# 12_CONSOLE.net
KiCad netlist of a schematic drawn in Altium Designer
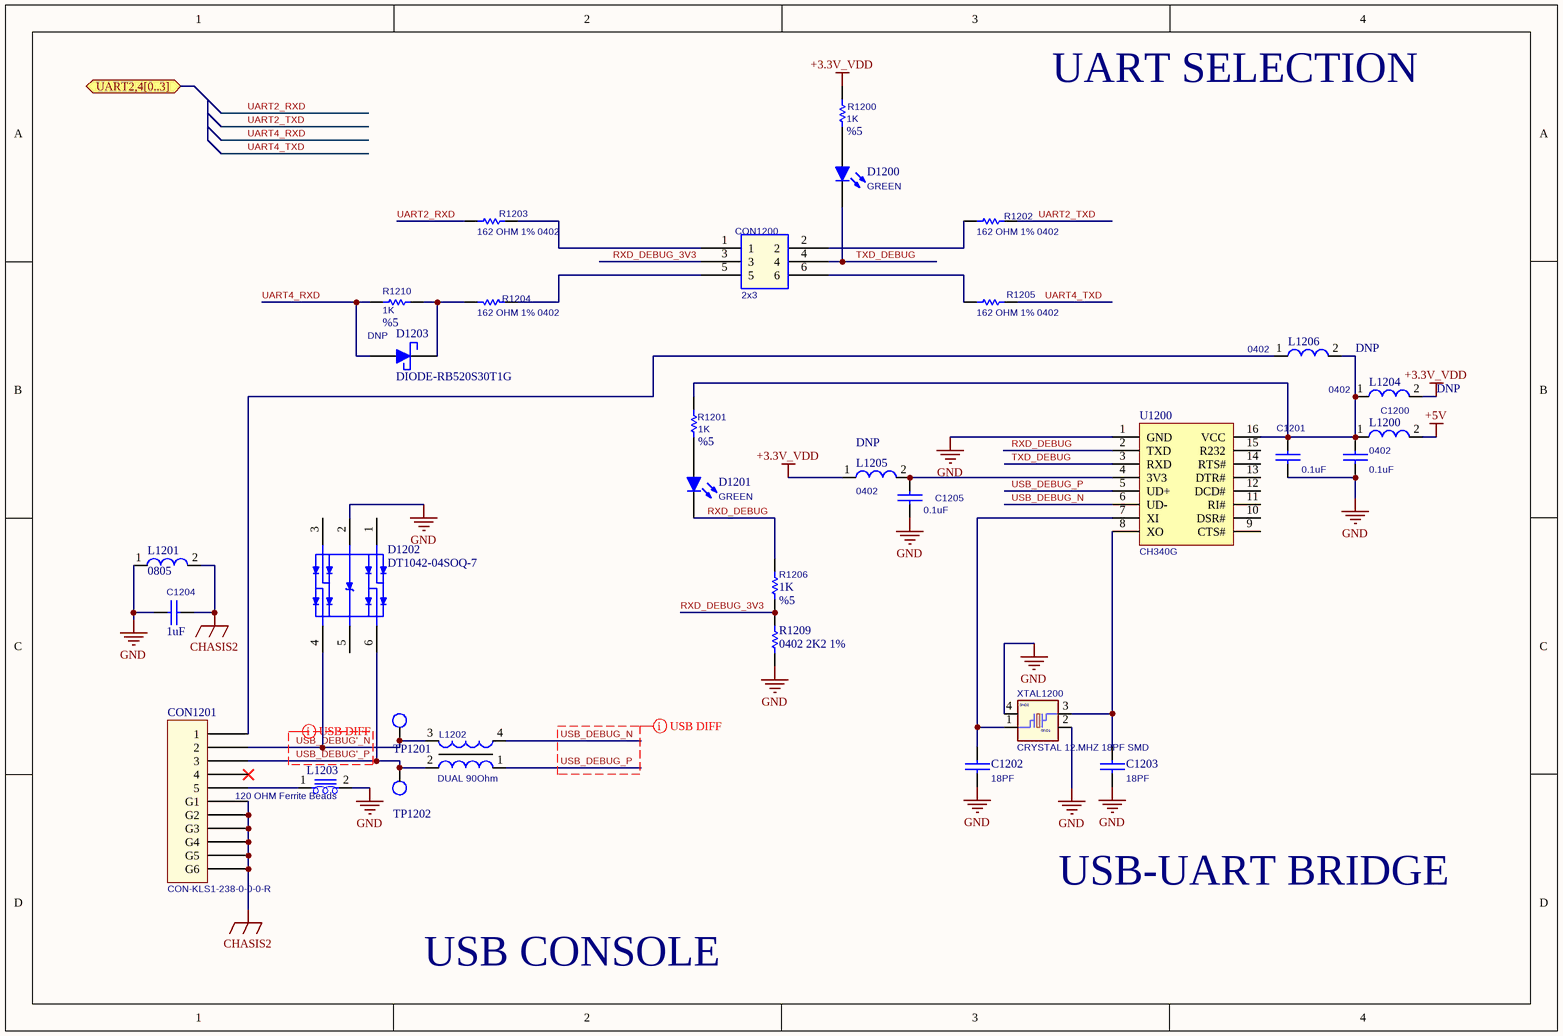
[diagram p0: 12 CONSOLE.SchDoc]

(export (version "E")
  (design (tool "Eeschema 10.0.6"))
  (components
    (comp (ref "C1200")
      (value "0.1uF")
      (footprint "0402_CC")
      (description "CAP VER 0.1UF 16V X7R 0402")
      (fields (field (name "CREATED BY") "LA") (field (name "CHECKED BY") "*"))
      (libsource (lib "ARETE_L") (part "CAP-CL05B104KO5NNNC"))
    )
    (comp (ref "C1201")
      (value "0.1uF")
      (footprint "0402_CC")
      (description "CAP VER 0.1UF 16V X7R 0402")
      (fields (field (name "CREATED BY") "LA") (field (name "CHECKED BY") "*"))
      (libsource (lib "ARETE_L") (part "CAP-CL05B104KO5NNNC"))
    )
    (comp (ref "C1202")
      (value "18PF")
      (footprint "0402_CC")
      (description "CAP CER 18PF 50V C0G/NP0 0402")
      (fields (field (name "CREATED BY") "*") (field (name "CHECKED BY") "*"))
      (libsource (lib "ARETE_SCH") (part "CAP-GCM1555C1H180JA16D"))
    )
    (comp (ref "C1203")
      (value "18PF")
      (footprint "0402_CC")
      (description "CAP CER 18PF 50V C0G/NP0 0402")
      (fields (field (name "CREATED BY") "*") (field (name "CHECKED BY") "*"))
      (libsource (lib "ARETE_SCH") (part "CAP-GCM1555C1H180JA16D"))
    )
    (comp (ref "C1204")
      (value "1uF")
      (footprint "0603_CC")
      (description "CAP CER 1UF 25V X7R 0603")
      (fields (field (name "CREATED BY") "LA") (field (name "CHECKED BY") "*"))
      (libsource (lib "ARETE_SCH") (part "CAP-CL10B105KA8NNNC"))
    )
    (comp (ref "C1205")
      (value "0.1uF")
      (footprint "0402_CC")
      (description "CAP VER 0.1UF 16V X7R 0402")
      (fields (field (name "CREATED BY") "LA") (field (name "CHECKED BY") "*"))
      (libsource (lib "ARETE_L") (part "CAP-CL05B104KO5NNNC"))
    )
    (comp (ref "CON1200")
      (value "2x3")
      (footprint "HEADER 2.54 X 3x2")
      (description "2x3 6 PIN 2.54MM HEADER")
      (fields
        (field (name "MANUFACTURER") "Wurth Electronics")
        (field (name "MANUFACTURER PART NUMBER") "61300621121")
        (field (name "CREATED BY") "*")
        (field (name "CHECKED BY") "*")
      )
      (libsource (lib "ARETE_SCH") (part "CON-6 PIN 2.54MM"))
    )
    (comp (ref "CON1201")
      (value "CON-KLS1-238-0-0-0-R")
      (footprint "KLS1-238-0-0-0-R")
      (fields (field (name "CREATED BY") "OKS,EE") (field (name "CHECKED BY") "*"))
      (libsource (lib "ARETE_SCH") (part "CON-KLS1-238-0-0-0-R"))
    )
    (comp (ref "D1200")
      (value "GREEN")
      (footprint "0603_LED")
      (description "LED SMD 0603 SUPER GREEN")
      (fields (field (name "CREATED BY") "*") (field (name "CHECKED BY") "*"))
      (libsource (lib "ARETE_SCH") (part "LED-LTST-C190KRKT"))
    )
    (comp (ref "D1201")
      (value "GREEN")
      (footprint "0603_LED")
      (description "LED SMD 0603 SUPER GREEN")
      (fields (field (name "CREATED BY") "*") (field (name "CHECKED BY") "*"))
      (libsource (lib "ARETE_SCH") (part "LED-LTST-C190KRKT"))
    )
    (comp (ref "D1202")
      (value "DT1042-04SOQ-7")
      (footprint "DIODE-DT1042-04SOQ-7")
      (description "HDMI TVS DIODE")
      (fields (field (name "CREATED BY") "E.E") (field (name "CHECKED BY") "*"))
      (libsource (lib "ARETE_SCH") (part "DIODE-DT1042-04SOQ-7"))
    )
    (comp (ref "D1203")
      (value "DIODE-RB520S30T1G")
      (footprint "SOD523")
      (description "DIODE SCHOTTKY 30V 200MA SOD523")
      (fields (field (name "CREATED BY") "LA") (field (name "CHECKED BY") "*"))
      (libsource (lib "ARETE_L") (part "DIODE-RB520S30T1G"))
    )
    (comp (ref "L1200")
      (value "0402")
      (footprint "0402_RES")
      (description "0OHM 0402")
      (fields (field (name "CREATED BY") "EE") (field (name "CHECKED BY") "*"))
      (libsource (lib "ARETE_SCH") (part "IND-FERRITE (RES 0 OHM) 0402"))
    )
    (comp (ref "L1201")
      (value "0805")
      (footprint "0805")
      (description "0OHM 0805")
      (fields (field (name "CREATED BY") "EE") (field (name "CHECKED BY") "*"))
      (libsource (lib "ARETE_SCH") (part "IND-FERRITE (RES 0 OHM) 0805"))
    )
    (comp (ref "L1202")
      (value "DUAL 90Ohm")
      (footprint "DLW21H")
      (description "Common Mode Chokes Dual 90Ohm 100MHz 0.33A 0.35Ohm DCR SMD T/R")
      (fields (field (name "CREATED BY") "E.E") (field (name "CHECKED BY") "*"))
      (libsource (lib "ARETE_SCH") (part "IND-DLW21HN900SQ2L"))
    )
    (comp (ref "L1203")
      (value "120 OHM Ferrite Beads")
      (footprint "0603_RES")
      (description "Ferrite Beads Multi-Layer 120Ohm 25% 100MHz 2A 0.05Ohm DCR 0603 Automotive T/R")
      (fields (field (name "CREATED BY") "E.E") (field (name "CHECKED BY") "*"))
      (libsource (lib "ARETE_SCH") (part "IND-BLM18PG121SH1D"))
    )
    (comp (ref "L1204")
      (value "0402")
      (footprint "0402_RES")
      (description "0OHM 0402")
      (fields
        (field (name "ASSY_OPT") "DNP")
        (field (name "CREATED BY") "EE")
        (field (name "CHECKED BY") "*")
      )
      (libsource (lib "ARETE_SCH") (part "IND-FERRITE (RES 0 OHM) 0402"))
    )
    (comp (ref "L1205")
      (value "0402")
      (footprint "0402_RES")
      (description "0OHM 0402")
      (fields
        (field (name "ASSY_OPT") "DNP")
        (field (name "CREATED BY") "EE")
        (field (name "CHECKED BY") "*")
      )
      (libsource (lib "ARETE_SCH") (part "IND-FERRITE (RES 0 OHM) 0402"))
    )
    (comp (ref "L1206")
      (value "0402")
      (footprint "0402_RES")
      (description "0OHM 0402")
      (fields
        (field (name "ASSY_OPT") "DNP")
        (field (name "CREATED BY") "EE")
        (field (name "CHECKED BY") "*")
      )
      (libsource (lib "ARETE_SCH") (part "IND-FERRITE (RES 0 OHM) 0402"))
    )
    (comp (ref "R1200")
      (value "1K")
      (footprint "0402_RES")
      (description "RES 1K OHM 5% 1/16W 0402")
      (fields
        (field (name "TOLERANCE") "%5")
        (field (name "CREATED BY") "LA")
        (field (name "CHECKED BY") "*")
      )
      (libsource (lib "ARETE_SCH") (part "RES-RMCF0402JT1K00"))
    )
    (comp (ref "R1201")
      (value "1K")
      (footprint "0402_RES")
      (description "RES 1K OHM 5% 1/16W 0402")
      (fields
        (field (name "TOLERANCE") "%5")
        (field (name "CREATED BY") "LA")
        (field (name "CHECKED BY") "*")
      )
      (libsource (lib "ARETE_SCH") (part "RES-RMCF0402JT1K00"))
    )
    (comp (ref "R1202")
      (value "162 OHM 1% 0402")
      (footprint "0402_RES")
      (description "162 ±1% 0.1W, 1/10W Chip Resistor 0402 (1005 Metric) Automotive AEC-Q200 Thick Film")
      (fields (field (name "CREATED BY") "E.E") (field (name "CHECKED BY") "*"))
      (libsource (lib "ARETE_SCH") (part "RES-ERJ-2RKF1620X"))
    )
    (comp (ref "R1203")
      (value "162 OHM 1% 0402")
      (footprint "0402_RES")
      (description "162 ±1% 0.1W, 1/10W Chip Resistor 0402 (1005 Metric) Automotive AEC-Q200 Thick Film")
      (fields (field (name "CREATED BY") "E.E") (field (name "CHECKED BY") "*"))
      (libsource (lib "ARETE_SCH") (part "RES-ERJ-2RKF1620X"))
    )
    (comp (ref "R1204")
      (value "162 OHM 1% 0402")
      (footprint "0402_RES")
      (description "162 ±1% 0.1W, 1/10W Chip Resistor 0402 (1005 Metric) Automotive AEC-Q200 Thick Film")
      (fields (field (name "CREATED BY") "E.E") (field (name "CHECKED BY") "*"))
      (libsource (lib "ARETE_SCH") (part "RES-ERJ-2RKF1620X"))
    )
    (comp (ref "R1205")
      (value "162 OHM 1% 0402")
      (footprint "0402_RES")
      (description "162 ±1% 0.1W, 1/10W Chip Resistor 0402 (1005 Metric) Automotive AEC-Q200 Thick Film")
      (fields (field (name "CREATED BY") "E.E") (field (name "CHECKED BY") "*"))
      (libsource (lib "ARETE_SCH") (part "RES-ERJ-2RKF1620X"))
    )
    (comp (ref "R1206")
      (value "1K")
      (footprint "0402_RES")
      (description "RES 1K OHM 5% 1/16W 0402")
      (fields
        (field (name "TOLERANCE") "%5")
        (field (name "CREATED BY") "LA")
        (field (name "CHECKED BY") "*")
      )
      (libsource (lib "ARETE_SCH") (part "RES-RMCF0402JT1K00"))
    )
    (comp (ref "R1209")
      (value "0402 2K2 1%")
      (footprint "0402_RES")
      (fields (field (name "CREATED BY") "E.E") (field (name "CHECKED BY") "*"))
      (libsource (lib "ARETE_V2_SCH") (part "RES-CRGCQ0402F2K2"))
    )
    (comp (ref "R1210")
      (value "1K")
      (footprint "0402_RES")
      (description "RES 1K OHM 5% 1/16W 0402")
      (fields
        (field (name "ASSY_OPT") "DNP")
        (field (name "TOLERANCE") "%5")
        (field (name "CREATED BY") "LA")
        (field (name "CHECKED BY") "*")
      )
      (libsource (lib "ARETE_SCH") (part "RES-RMCF0402JT1K00"))
    )
    (comp (ref "TP1201")
      (value "TEST POINT 15")
      (footprint "testpoint_15")
      (libsource (lib "ARETE_L") (part "TEST POINT 15"))
    )
    (comp (ref "TP1202")
      (value "TEST POINT 15")
      (footprint "testpoint_15")
      (libsource (lib "ARETE_L") (part "TEST POINT 15"))
    )
    (comp (ref "U1200")
      (value "CH340G")
      (footprint "CH340G")
      (description "IC-340 USB INTERFACE SO16")
      (fields (field (name "CREATED BY") "E.E.") (field (name "CHECKED BY") "*"))
      (libsource (lib "ARETE_SCH") (part "IC-CH340G"))
    )
    (comp (ref "XTAL1200")
      (value "CRYSTAL 12.MHZ 18PF SMD")
      (footprint "XTLOSC4_3P2X2P5MM_SM")
      (description "CRYSTAL 12.0000MHZ 18PF SMD")
      (fields (field (name "CREATED BY") "E.E") (field (name "CHECKED BY") "*"))
      (libsource (lib "ARETE_SCH") (part "XTAL-FA-238V 12.0000MB50X-C0"))
    )
  )
  (nets
    (net (code "5") (name "+3.3V_VDD") (class "Default")
      (node (ref "L1204") (pin "2") (pinfunction "2_2") (pintype "passive"))
      (node (ref "L1205") (pin "1") (pinfunction "1_1") (pintype "passive"))
      (node (ref "R1200") (pin "1") (pinfunction "1_1") (pintype "passive"))
    )
    (net (code "6") (name "+5V") (class "Default")
      (node (ref "L1200") (pin "2") (pinfunction "2_2") (pintype "passive"))
    )
    (net (code "7") (name "/RXD_DEBUG") (class "Default")
      (node (ref "D1201") (pin "2") (pinfunction "K_2") (pintype "passive"))
      (node (ref "R1206") (pin "2") (pinfunction "2_2") (pintype "passive"))
      (node (ref "U1200") (pin "2") (pinfunction "TXD_2") (pintype "passive"))
    )
    (net (code "8") (name "/RXD_DEBUG_3V3") (class "Default")
      (node (ref "CON1200") (pin "3") (pinfunction "3_3") (pintype "passive"))
      (node (ref "R1206") (pin "1") (pinfunction "1_1") (pintype "passive"))
      (node (ref "R1209") (pin "2") (pinfunction "2_2") (pintype "passive"))
    )
    (net (code "9") (name "/TXD_DEBUG") (class "Default")
      (node (ref "CON1200") (pin "4") (pinfunction "4_4") (pintype "passive"))
      (node (ref "D1200") (pin "2") (pinfunction "K_2") (pintype "passive"))
      (node (ref "U1200") (pin "3") (pinfunction "RXD_3") (pintype "passive"))
    )
    (net (code "11") (name "/UART2_RXD") (class "Default")
      (node (ref "R1203") (pin "1") (pinfunction "1_1") (pintype "passive"))
    )
    (net (code "12") (name "/UART2_TXD") (class "Default")
      (node (ref "R1202") (pin "2") (pinfunction "2_2") (pintype "passive"))
    )
    (net (code "13") (name "/UART4_RXD") (class "Default")
      (node (ref "D1203") (pin "1") (pinfunction "A_1") (pintype "passive"))
      (node (ref "R1210") (pin "1") (pinfunction "1_1") (pintype "passive"))
    )
    (net (code "14") (name "/UART4_TXD") (class "Default")
      (node (ref "R1205") (pin "2") (pinfunction "2_2") (pintype "passive"))
    )
    (net (code "15") (name "/USB_DEBUG'_N") (class "Default")
      (node (ref "CON1201") (pin "2") (pinfunction "2_2") (pintype "passive"))
      (node (ref "D1202") (pin "4") (pinfunction "IO3_4") (pintype "passive"))
      (node (ref "L1202") (pin "3") (pinfunction "3_3") (pintype "passive"))
      (node (ref "TP1201") (pin "1") (pinfunction "1_1") (pintype "passive"))
    )
    (net (code "16") (name "/USB_DEBUG'_P") (class "Default")
      (node (ref "CON1201") (pin "3") (pinfunction "3_3") (pintype "passive"))
      (node (ref "D1202") (pin "6") (pinfunction "IO4_6") (pintype "passive"))
      (node (ref "L1202") (pin "2") (pinfunction "2_2") (pintype "passive"))
      (node (ref "TP1202") (pin "1") (pinfunction "1_1") (pintype "passive"))
    )
    (net (code "17") (name "/USB_DEBUG_N") (class "Default")
      (node (ref "L1202") (pin "4") (pinfunction "4_4") (pintype "passive"))
      (node (ref "U1200") (pin "6") (pinfunction "UD-_6") (pintype "passive"))
    )
    (net (code "18") (name "/USB_DEBUG_P") (class "Default")
      (node (ref "L1202") (pin "1") (pinfunction "1_1") (pintype "passive"))
      (node (ref "U1200") (pin "5") (pinfunction "UD+_5") (pintype "passive"))
    )
    (net (code "19") (name "CHASIS2") (class "Default")
      (node (ref "C1204") (pin "1") (pinfunction "1_1") (pintype "passive"))
      (node (ref "CON1201") (pin "G1") (pinfunction "G1_G1") (pintype "passive"))
      (node (ref "CON1201") (pin "G2") (pinfunction "G2_G2") (pintype "passive"))
      (node (ref "CON1201") (pin "G3") (pinfunction "G3_G3") (pintype "passive"))
      (node (ref "CON1201") (pin "G4") (pinfunction "G4_G4") (pintype "passive"))
      (node (ref "CON1201") (pin "G5") (pinfunction "G5_G5") (pintype "passive"))
      (node (ref "CON1201") (pin "G6") (pinfunction "G6_G6") (pintype "passive"))
      (node (ref "L1201") (pin "2") (pinfunction "2_2") (pintype "passive"))
    )
    (net (code "20") (name "GND") (class "Default")
      (node (ref "C1200") (pin "2") (pinfunction "2_2") (pintype "passive"))
      (node (ref "C1201") (pin "2") (pinfunction "2_2") (pintype "passive"))
      (node (ref "C1202") (pin "2") (pinfunction "2_2") (pintype "passive"))
      (node (ref "C1203") (pin "2") (pinfunction "2_2") (pintype "passive"))
      (node (ref "C1204") (pin "2") (pinfunction "2_2") (pintype "passive"))
      (node (ref "C1205") (pin "2") (pinfunction "2_2") (pintype "passive"))
      (node (ref "D1202") (pin "2") (pinfunction "VSS_2") (pintype "power_in"))
      (node (ref "L1201") (pin "1") (pinfunction "1_1") (pintype "passive"))
      (node (ref "L1203") (pin "2") (pinfunction "2_2") (pintype "passive"))
      (node (ref "R1209") (pin "1") (pinfunction "1_1") (pintype "passive"))
      (node (ref "U1200") (pin "1") (pinfunction "GND_1") (pintype "passive"))
      (node (ref "XTAL1200") (pin "2") (pinfunction "GND1_2") (pintype "power_in"))
      (node (ref "XTAL1200") (pin "4") (pinfunction "GND2_4") (pintype "power_in"))
    )
    (net (code "21") (name "Net-(CON1200-Pad1)") (class "Default")
      (node (ref "CON1200") (pin "1") (pinfunction "1_1") (pintype "passive"))
      (node (ref "R1203") (pin "2") (pinfunction "2_2") (pintype "passive"))
    )
    (net (code "22") (name "Net-(CON1200-Pad2)") (class "Default")
      (node (ref "CON1200") (pin "2") (pinfunction "2_2") (pintype "passive"))
      (node (ref "R1202") (pin "1") (pinfunction "1_1") (pintype "passive"))
    )
    (net (code "23") (name "Net-(CON1200-Pad5)") (class "Default")
      (node (ref "CON1200") (pin "5") (pinfunction "5_5") (pintype "passive"))
      (node (ref "R1204") (pin "2") (pinfunction "2_2") (pintype "passive"))
    )
    (net (code "24") (name "Net-(CON1200-Pad6)") (class "Default")
      (node (ref "CON1200") (pin "6") (pinfunction "6_6") (pintype "passive"))
      (node (ref "R1205") (pin "1") (pinfunction "1_1") (pintype "passive"))
    )
    (net (code "25") (name "Net-(CON1201-Pad1)") (class "Default")
      (node (ref "CON1201") (pin "1") (pinfunction "1_1") (pintype "passive"))
      (node (ref "L1206") (pin "1") (pinfunction "1_1") (pintype "passive"))
    )
    (net (code "26") (name "Net-(CON1201-Pad5)") (class "Default")
      (node (ref "CON1201") (pin "5") (pinfunction "5_5") (pintype "passive"))
      (node (ref "L1203") (pin "1") (pinfunction "1_1") (pintype "passive"))
    )
    (net (code "27") (name "Net-(D1200-A)") (class "Default")
      (node (ref "D1200") (pin "1") (pinfunction "A_1") (pintype "passive"))
      (node (ref "R1200") (pin "2") (pinfunction "2_2") (pintype "passive"))
    )
    (net (code "28") (name "Net-(D1201-A)") (class "Default")
      (node (ref "D1201") (pin "1") (pinfunction "A_1") (pintype "passive"))
      (node (ref "R1201") (pin "2") (pinfunction "2_2") (pintype "passive"))
    )
    (net (code "29") (name "Net-(D1203-K)") (class "Default")
      (node (ref "D1203") (pin "2") (pinfunction "K_2") (pintype "passive"))
      (node (ref "R1204") (pin "1") (pinfunction "1_1") (pintype "passive"))
      (node (ref "R1210") (pin "2") (pinfunction "2_2") (pintype "passive"))
    )
    (net (code "30") (name "Net-(U1200-3V3)") (class "Default")
      (node (ref "C1205") (pin "1") (pinfunction "1_1") (pintype "passive"))
      (node (ref "L1205") (pin "2") (pinfunction "2_2") (pintype "passive"))
      (node (ref "U1200") (pin "4") (pinfunction "3V3_4") (pintype "passive"))
    )
    (net (code "31") (name "Net-(U1200-VCC)") (class "Default")
      (node (ref "C1200") (pin "1") (pinfunction "1_1") (pintype "passive"))
      (node (ref "C1201") (pin "1") (pinfunction "1_1") (pintype "passive"))
      (node (ref "L1200") (pin "1") (pinfunction "1_1") (pintype "passive"))
      (node (ref "L1204") (pin "1") (pinfunction "1_1") (pintype "passive"))
      (node (ref "L1206") (pin "2") (pinfunction "2_2") (pintype "passive"))
      (node (ref "R1201") (pin "1") (pinfunction "1_1") (pintype "passive"))
      (node (ref "U1200") (pin "16") (pinfunction "VCC_16") (pintype "passive"))
    )
    (net (code "32") (name "Net-(U1200-XI)") (class "Default")
      (node (ref "C1202") (pin "1") (pinfunction "1_1") (pintype "passive"))
      (node (ref "U1200") (pin "7") (pinfunction "XI_7") (pintype "passive"))
      (node (ref "XTAL1200") (pin "1") (pinfunction "1_1") (pintype "passive"))
    )
    (net (code "33") (name "Net-(U1200-XO)") (class "Default")
      (node (ref "C1203") (pin "1") (pinfunction "1_1") (pintype "passive"))
      (node (ref "U1200") (pin "8") (pinfunction "XO_8") (pintype "passive"))
      (node (ref "XTAL1200") (pin "3") (pinfunction "3_3") (pintype "passive"))
    )
    (net (code "34") (name "unconnected-(CON1201-Pad4)") (class "Default")
      (node (ref "CON1201") (pin "4") (pinfunction "4_4") (pintype "passive+no_connect"))
    )
    (net (code "35") (name "unconnected-(D1202-IO1-Pad1)") (class "Default")
      (node (ref "D1202") (pin "1") (pinfunction "IO1_1") (pintype "passive"))
    )
    (net (code "36") (name "unconnected-(D1202-IO2-Pad3)") (class "Default")
      (node (ref "D1202") (pin "3") (pinfunction "IO2_3") (pintype "passive"))
    )
    (net (code "37") (name "unconnected-(D1202-VCC-Pad5)") (class "Default")
      (node (ref "D1202") (pin "5") (pinfunction "VCC_5") (pintype "power_in"))
    )
    (net (code "38") (name "unconnected-(U1200-CTS#-Pad9)") (class "Default")
      (node (ref "U1200") (pin "9") (pinfunction "CTS#_9") (pintype "passive"))
    )
    (net (code "39") (name "unconnected-(U1200-DCD#-Pad12)") (class "Default")
      (node (ref "U1200") (pin "12") (pinfunction "DCD#_12") (pintype "passive"))
    )
    (net (code "40") (name "unconnected-(U1200-DSR#-Pad10)") (class "Default")
      (node (ref "U1200") (pin "10") (pinfunction "DSR#_10") (pintype "passive"))
    )
    (net (code "41") (name "unconnected-(U1200-DTR#-Pad13)") (class "Default")
      (node (ref "U1200") (pin "13") (pinfunction "DTR#_13") (pintype "passive"))
    )
    (net (code "42") (name "unconnected-(U1200-R232-Pad15)") (class "Default")
      (node (ref "U1200") (pin "15") (pinfunction "R232_15") (pintype "passive"))
    )
    (net (code "43") (name "unconnected-(U1200-RI#-Pad11)") (class "Default")
      (node (ref "U1200") (pin "11") (pinfunction "RI#_11") (pintype "passive"))
    )
    (net (code "44") (name "unconnected-(U1200-RTS#-Pad14)") (class "Default")
      (node (ref "U1200") (pin "14") (pinfunction "RTS#_14") (pintype "passive"))
    )
  )
)
